# stm32-2inch40.net
KiCad netlist of a schematic drawn in EAGLE
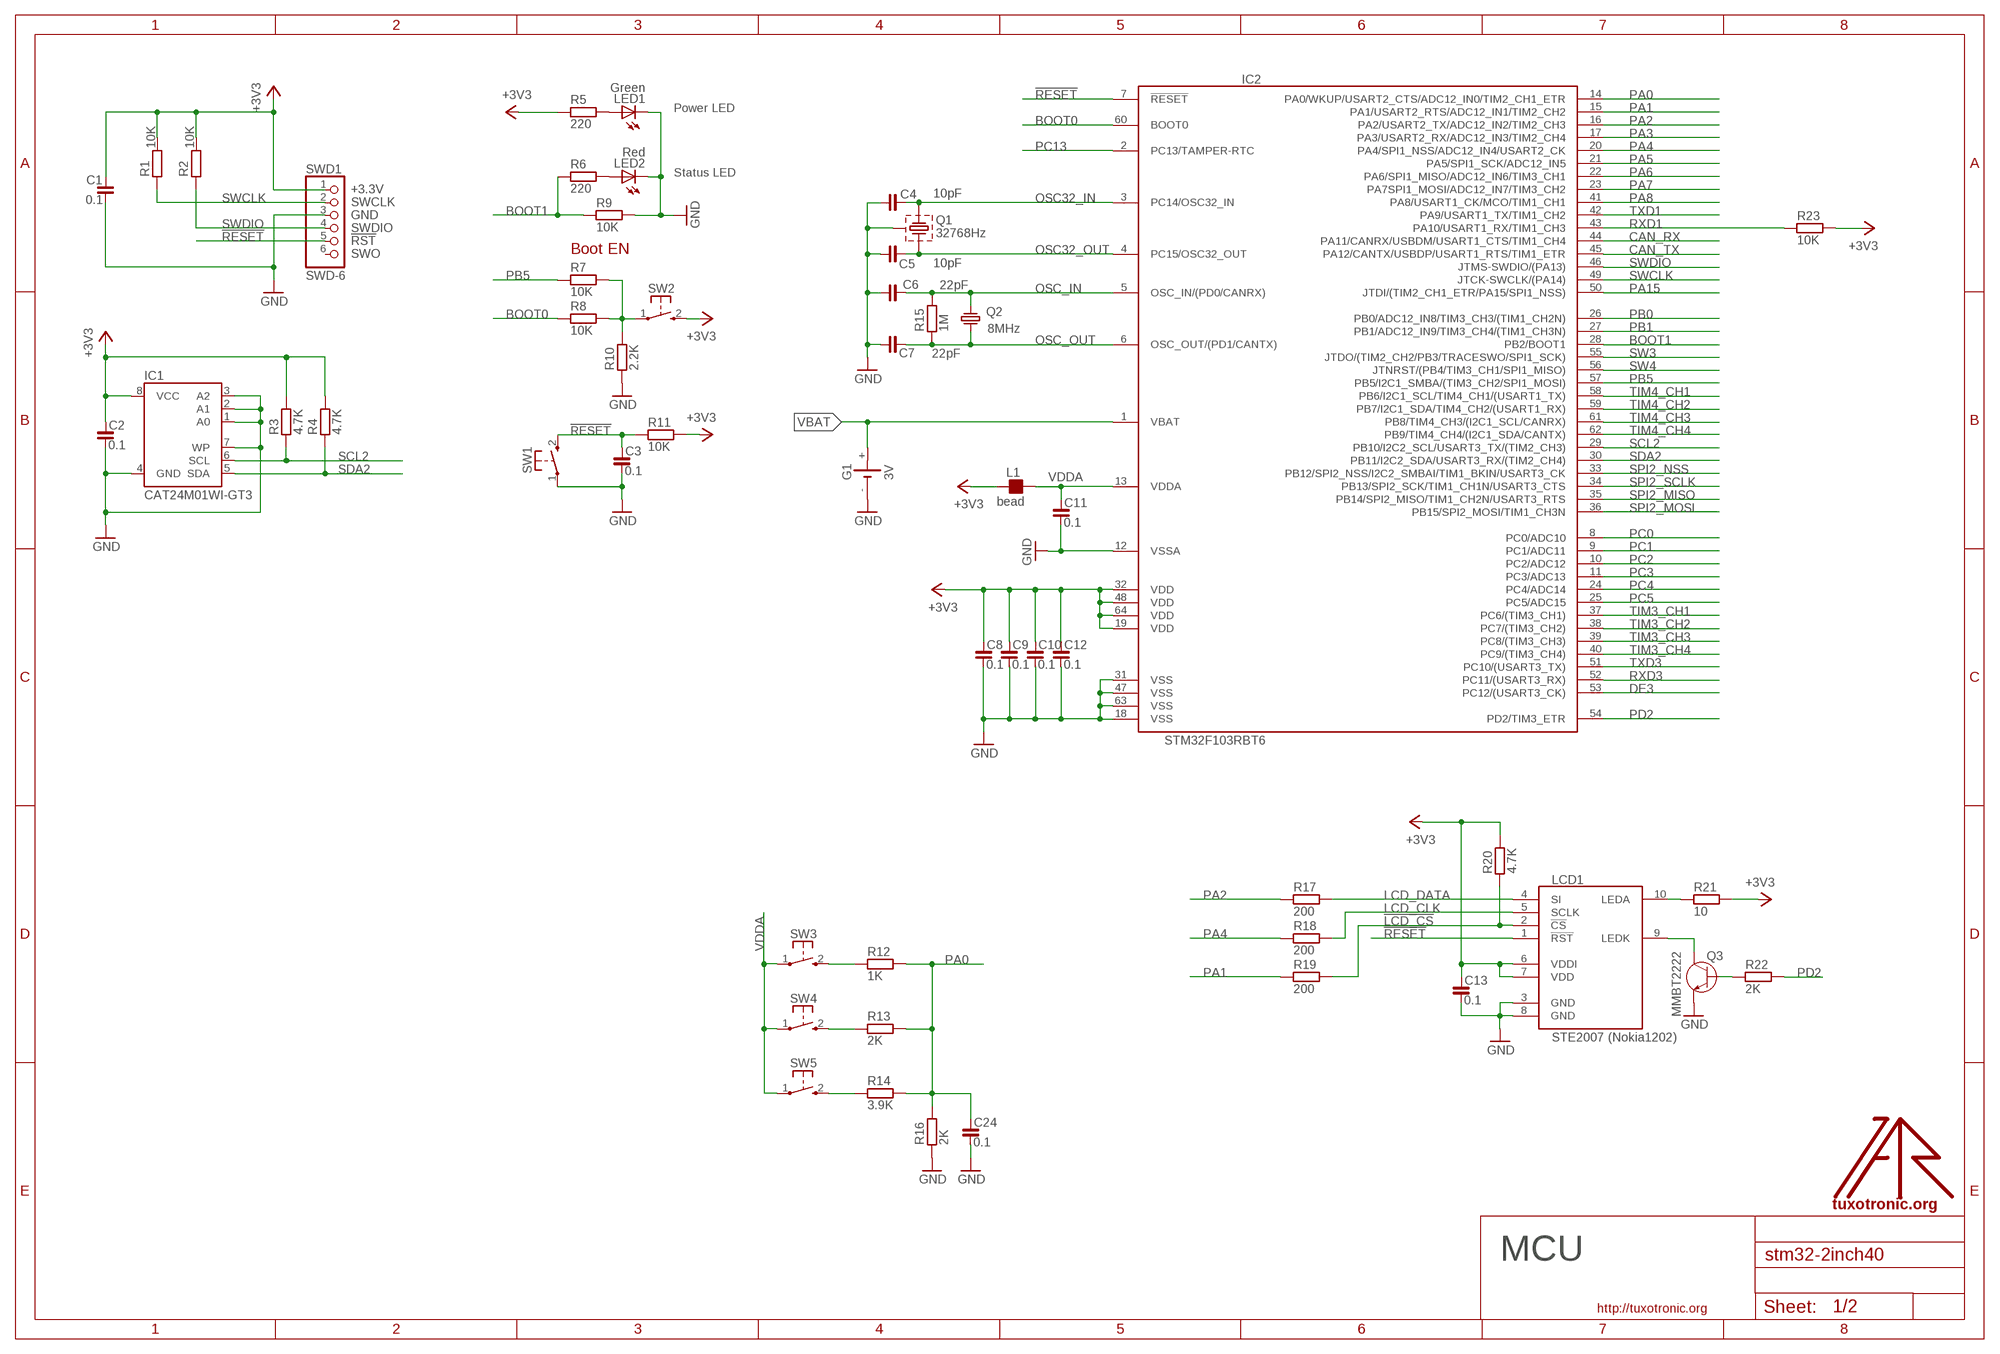
[diagram p0: schematic, sheet 1]
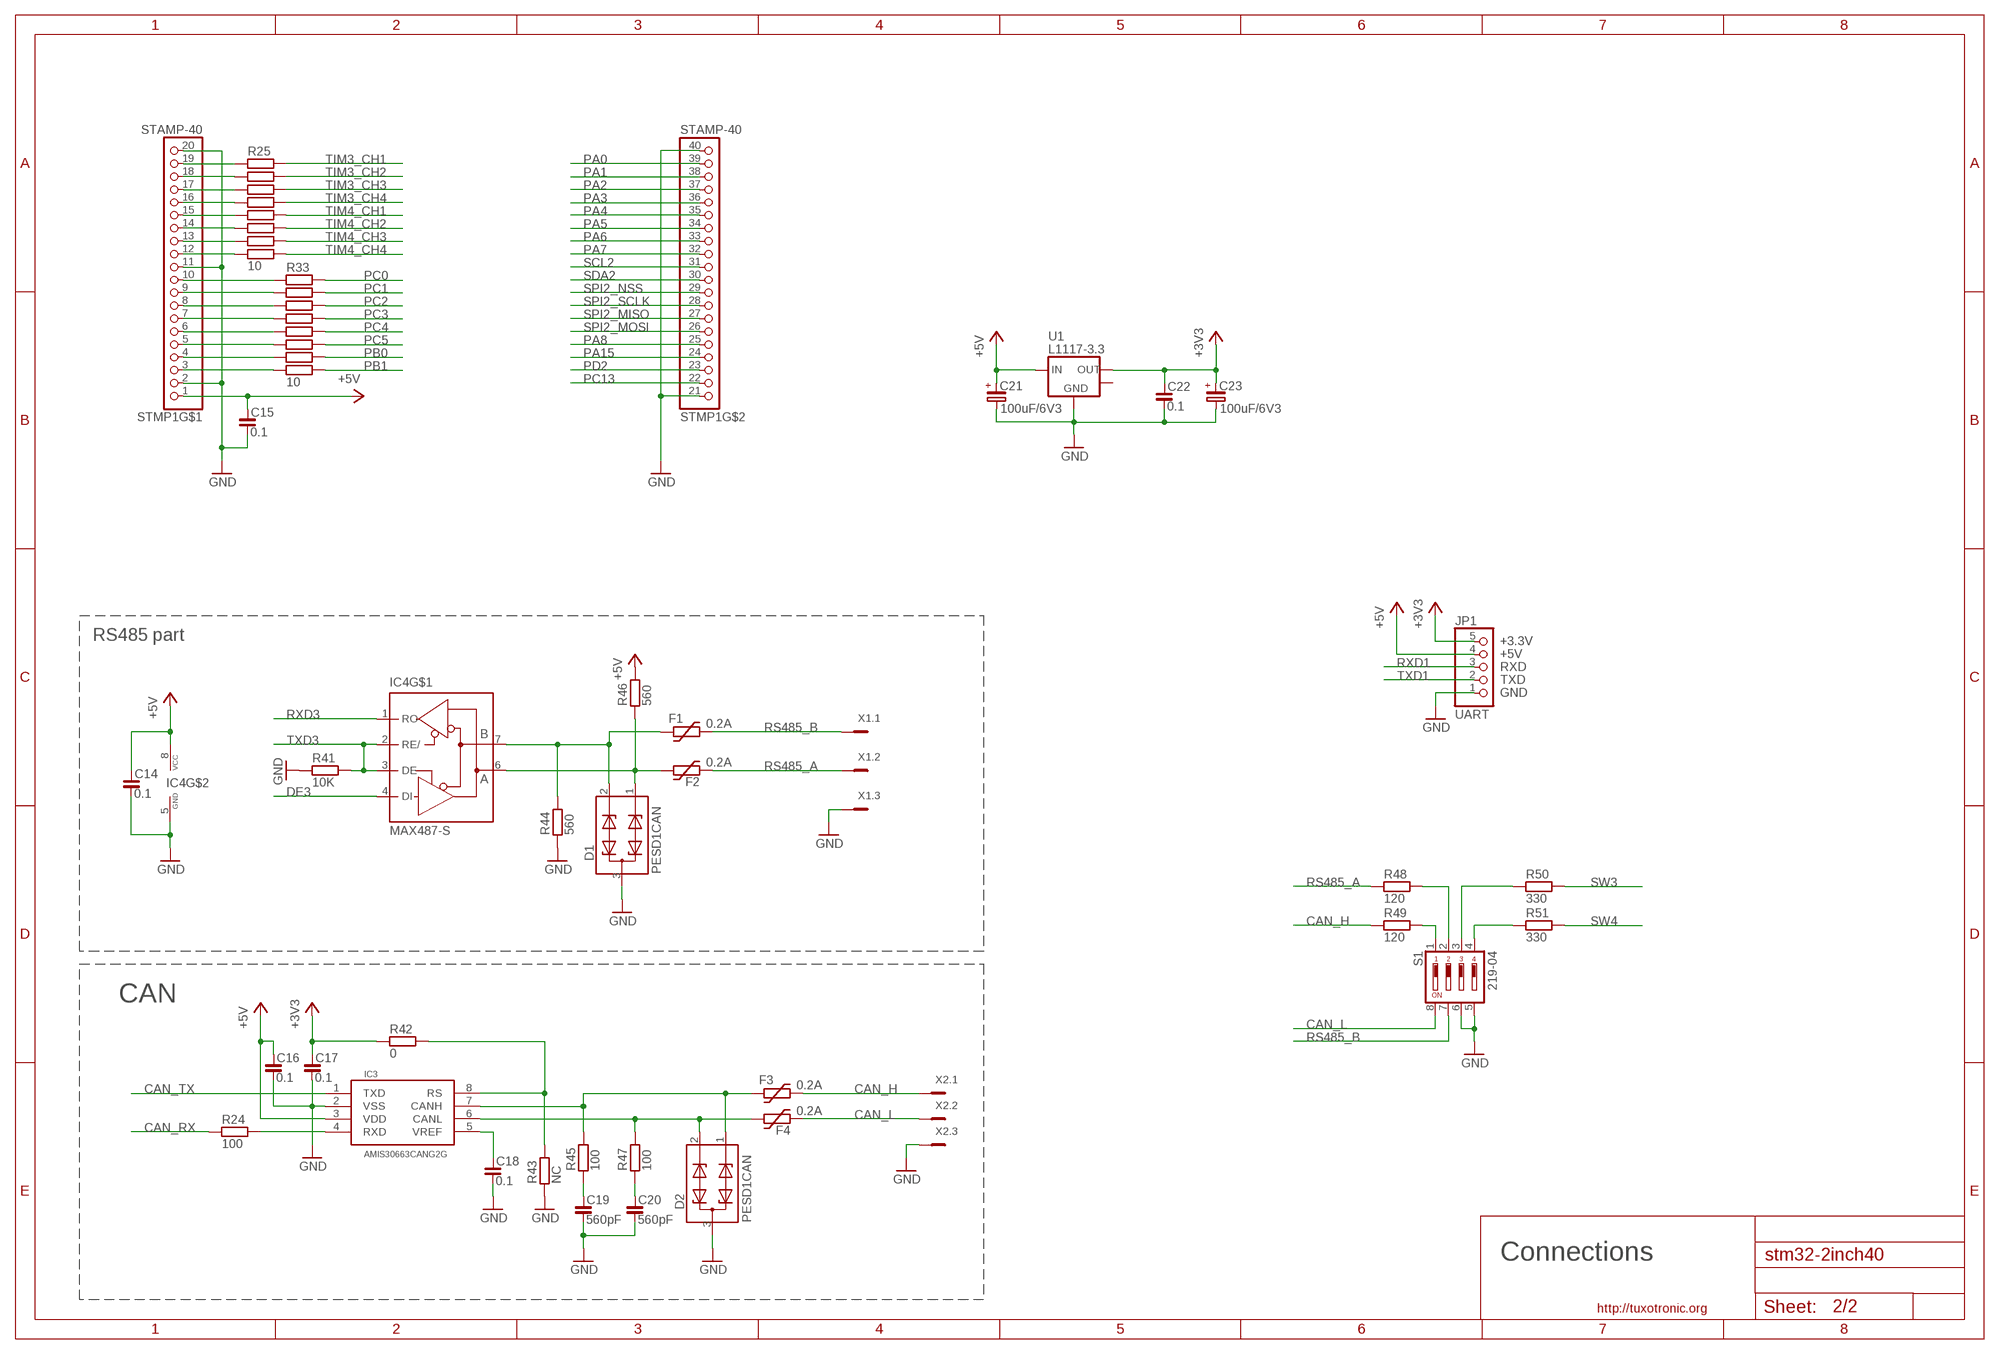
[diagram p1: schematic, sheet 2]

(export (version "E")
  (design (tool "Eeschema 10.0.6"))
  (components
    (comp (ref "C14")
      (value "0.1")
      (footprint "eagle-import:C0603")
      (libsource (lib "eagle-import") (part "C_0603"))
    )
    (comp (ref "C15")
      (value "0.1")
      (footprint "eagle-import:C0805")
      (libsource (lib "eagle-import") (part "C_0805"))
    )
    (comp (ref "C16")
      (value "0.1")
      (footprint "eagle-import:C0603")
      (libsource (lib "eagle-import") (part "C_0603"))
    )
    (comp (ref "C17")
      (value "0.1")
      (footprint "eagle-import:C0603")
      (libsource (lib "eagle-import") (part "C_0603"))
    )
    (comp (ref "C18")
      (value "0.1")
      (footprint "eagle-import:C0603")
      (libsource (lib "eagle-import") (part "C_0603"))
    )
    (comp (ref "C19")
      (value "560pF")
      (footprint "eagle-import:C0603")
      (libsource (lib "eagle-import") (part "C_0603"))
    )
    (comp (ref "C20")
      (value "560pF")
      (footprint "eagle-import:C0603")
      (libsource (lib "eagle-import") (part "C_0603"))
    )
    (comp (ref "C21")
      (value "100uF/6V3")
      (footprint "eagle-import:SMC_D")
      (libsource (lib "eagle-import") (part "CP_SMCD"))
    )
    (comp (ref "C22")
      (value "0.1")
      (footprint "eagle-import:C0805")
      (libsource (lib "eagle-import") (part "C_0805"))
    )
    (comp (ref "C23")
      (value "100uF/6V3")
      (footprint "eagle-import:SMC_D")
      (libsource (lib "eagle-import") (part "CP_SMCD"))
    )
    (comp (ref "D1")
      (value "PESD1CAN")
      (footprint "eagle-import:SOT23")
      (libsource (lib "eagle-import") (part "PESD1CAN"))
    )
    (comp (ref "D2")
      (value "PESD1CAN")
      (footprint "eagle-import:SOT23")
      (libsource (lib "eagle-import") (part "PESD1CAN"))
    )
    (comp (ref "F1")
      (value "0.2A")
      (footprint "eagle-import:1206L")
      (libsource (lib "eagle-import") (part "1206L"))
    )
    (comp (ref "F2")
      (value "0.2A")
      (footprint "eagle-import:1206L")
      (libsource (lib "eagle-import") (part "1206L"))
    )
    (comp (ref "F3")
      (value "0.2A")
      (footprint "eagle-import:1206L")
      (libsource (lib "eagle-import") (part "1206L"))
    )
    (comp (ref "F4")
      (value "0.2A")
      (footprint "eagle-import:1206L")
      (libsource (lib "eagle-import") (part "1206L"))
    )
    (comp (ref "IC3")
      (value "AMIS30663CANG2G")
      (footprint "eagle-import:SO08")
      (libsource (lib "eagle-import") (part "SN65HVD230"))
    )
    (comp (ref "IC4")
      (value "MAX487-S")
      (footprint "eagle-import:SO08")
      (libsource (lib "eagle-import") (part "MAX487-S"))
    )
    (comp (ref "JP1")
      (value "UART")
      (footprint "eagle-import:UART_1X05")
      (libsource (lib "eagle-import") (part "UART-5_2.54"))
    )
    (comp (ref "R24")
      (value "100")
      (footprint "eagle-import:R0603")
      (libsource (lib "eagle-import") (part "R_0603"))
    )
    (comp (ref "R25")
      (value "10")
      (footprint "eagle-import:R0603")
      (libsource (lib "eagle-import") (part "R_0603"))
    )
    (comp (ref "R26")
      (value "10")
      (footprint "eagle-import:R0603")
      (libsource (lib "eagle-import") (part "R_0603"))
    )
    (comp (ref "R27")
      (value "10")
      (footprint "eagle-import:R0603")
      (libsource (lib "eagle-import") (part "R_0603"))
    )
    (comp (ref "R28")
      (value "10")
      (footprint "eagle-import:R0603")
      (libsource (lib "eagle-import") (part "R_0603"))
    )
    (comp (ref "R29")
      (value "10")
      (footprint "eagle-import:R0603")
      (libsource (lib "eagle-import") (part "R_0603"))
    )
    (comp (ref "R30")
      (value "10")
      (footprint "eagle-import:R0603")
      (libsource (lib "eagle-import") (part "R_0603"))
    )
    (comp (ref "R31")
      (value "10")
      (footprint "eagle-import:R0603")
      (libsource (lib "eagle-import") (part "R_0603"))
    )
    (comp (ref "R32")
      (value "10")
      (footprint "eagle-import:R0603")
      (libsource (lib "eagle-import") (part "R_0603"))
    )
    (comp (ref "R33")
      (value "10")
      (footprint "eagle-import:R0603")
      (libsource (lib "eagle-import") (part "R_0603"))
    )
    (comp (ref "R34")
      (value "10")
      (footprint "eagle-import:R0603")
      (libsource (lib "eagle-import") (part "R_0603"))
    )
    (comp (ref "R35")
      (value "10")
      (footprint "eagle-import:R0603")
      (libsource (lib "eagle-import") (part "R_0603"))
    )
    (comp (ref "R36")
      (value "10")
      (footprint "eagle-import:R0603")
      (libsource (lib "eagle-import") (part "R_0603"))
    )
    (comp (ref "R37")
      (value "10")
      (footprint "eagle-import:R0603")
      (libsource (lib "eagle-import") (part "R_0603"))
    )
    (comp (ref "R38")
      (value "10")
      (footprint "eagle-import:R0603")
      (libsource (lib "eagle-import") (part "R_0603"))
    )
    (comp (ref "R39")
      (value "10")
      (footprint "eagle-import:R0603")
      (libsource (lib "eagle-import") (part "R_0603"))
    )
    (comp (ref "R40")
      (value "10")
      (footprint "eagle-import:R0603")
      (libsource (lib "eagle-import") (part "R_0603"))
    )
    (comp (ref "R41")
      (value "10K")
      (footprint "eagle-import:R0603")
      (libsource (lib "eagle-import") (part "R_0603"))
    )
    (comp (ref "R42")
      (value "0")
      (footprint "eagle-import:R0603")
      (libsource (lib "eagle-import") (part "R_0603"))
    )
    (comp (ref "R43")
      (value "NC")
      (footprint "eagle-import:R0603")
      (libsource (lib "eagle-import") (part "R_0603"))
    )
    (comp (ref "R44")
      (value "560")
      (footprint "eagle-import:R0603")
      (libsource (lib "eagle-import") (part "R_0603"))
    )
    (comp (ref "R45")
      (value "100")
      (footprint "eagle-import:R0603")
      (libsource (lib "eagle-import") (part "R_0603"))
    )
    (comp (ref "R46")
      (value "560")
      (footprint "eagle-import:R0603")
      (libsource (lib "eagle-import") (part "R_0603"))
    )
    (comp (ref "R47")
      (value "100")
      (footprint "eagle-import:R0603")
      (libsource (lib "eagle-import") (part "R_0603"))
    )
    (comp (ref "R48")
      (value "120")
      (footprint "eagle-import:R0805")
      (libsource (lib "eagle-import") (part "R_0805"))
    )
    (comp (ref "R49")
      (value "120")
      (footprint "eagle-import:R0805")
      (libsource (lib "eagle-import") (part "R_0805"))
    )
    (comp (ref "R50")
      (value "330")
      (footprint "eagle-import:R0603")
      (libsource (lib "eagle-import") (part "R_0603"))
    )
    (comp (ref "R51")
      (value "330")
      (footprint "eagle-import:R0603")
      (libsource (lib "eagle-import") (part "R_0603"))
    )
    (comp (ref "S1")
      (value "219-04")
      (footprint "eagle-import:CTS-219-04")
      (libsource (lib "eagle-import") (part "219-04"))
    )
    (comp (ref "STMP1")
      (value "STAMP-40")
      (footprint "eagle-import:STAMP-40")
      (libsource (lib "eagle-import") (part "STAMP-40"))
    )
    (comp (ref "U1")
      (value "L1117-3.3")
      (footprint "eagle-import:SOT223")
      (libsource (lib "eagle-import") (part "LM1117-3.3"))
    )
    (comp (ref "X1")
      (value "MCV3")
      (footprint "eagle-import:MCV3")
      (libsource (lib "eagle-import") (part "MCV3"))
    )
    (comp (ref "X2")
      (value "MCV3")
      (footprint "eagle-import:MCV3")
      (libsource (lib "eagle-import") (part "MCV3"))
    )
    (comp (ref "C1")
      (value "0.1")
      (footprint "eagle-import:C0603")
      (libsource (lib "eagle-import") (part "C_0603"))
    )
    (comp (ref "C2")
      (value "0.1")
      (footprint "eagle-import:C0603")
      (libsource (lib "eagle-import") (part "C_0603"))
    )
    (comp (ref "C3")
      (value "0.1")
      (footprint "eagle-import:C0603")
      (libsource (lib "eagle-import") (part "C_0603"))
    )
    (comp (ref "C4")
      (value "10pF")
      (footprint "eagle-import:C0603")
      (libsource (lib "eagle-import") (part "C_0603"))
    )
    (comp (ref "C5")
      (value "10pF")
      (footprint "eagle-import:C0603")
      (libsource (lib "eagle-import") (part "C_0603"))
    )
    (comp (ref "C6")
      (value "22pF")
      (footprint "eagle-import:C0603")
      (libsource (lib "eagle-import") (part "C_0603"))
    )
    (comp (ref "C7")
      (value "22pF")
      (footprint "eagle-import:C0603")
      (libsource (lib "eagle-import") (part "C_0603"))
    )
    (comp (ref "C8")
      (value "0.1")
      (footprint "eagle-import:C0603")
      (libsource (lib "eagle-import") (part "C_0603"))
    )
    (comp (ref "C9")
      (value "0.1")
      (footprint "eagle-import:C0603")
      (libsource (lib "eagle-import") (part "C_0603"))
    )
    (comp (ref "C10")
      (value "0.1")
      (footprint "eagle-import:C0603")
      (libsource (lib "eagle-import") (part "C_0603"))
    )
    (comp (ref "C11")
      (value "0.1")
      (footprint "eagle-import:C0603")
      (libsource (lib "eagle-import") (part "C_0603"))
    )
    (comp (ref "C12")
      (value "0.1")
      (footprint "eagle-import:C0603")
      (libsource (lib "eagle-import") (part "C_0603"))
    )
    (comp (ref "C13")
      (value "0.1")
      (footprint "eagle-import:C0603")
      (libsource (lib "eagle-import") (part "C_0603"))
    )
    (comp (ref "C24")
      (value "0.1")
      (footprint "eagle-import:C0603")
      (libsource (lib "eagle-import") (part "C_0603"))
    )
    (comp (ref "G1")
      (value "3V")
      (footprint "eagle-import:SMT1220")
      (libsource (lib "eagle-import") (part "1220SMT"))
    )
    (comp (ref "IC1")
      (value "CAT24M01WI-GT3")
      (footprint "eagle-import:SO08")
      (libsource (lib "eagle-import") (part "AT24CS256"))
    )
    (comp (ref "IC2")
      (value "STM32F103RBT6")
      (footprint "eagle-import:TQFP64")
      (libsource (lib "eagle-import") (part "STM32F103R"))
    )
    (comp (ref "L1")
      (value "bead")
      (footprint "eagle-import:L0603")
      (libsource (lib "eagle-import") (part "FB_0603"))
    )
    (comp (ref "LCD1")
      (value "STE2007 (Nokia1202)")
      (footprint "eagle-import:NOKIA1202LCD-EXT")
      (libsource (lib "eagle-import") (part "LCD1202-EXT"))
    )
    (comp (ref "LED1")
      (value "Green")
      (footprint "eagle-import:CHIP-LED0805")
      (libsource (lib "eagle-import") (part "LEDCHIP-LED0805"))
    )
    (comp (ref "LED2")
      (value "Red")
      (footprint "eagle-import:CHIP-LED0805")
      (libsource (lib "eagle-import") (part "LEDCHIP-LED0805"))
    )
    (comp (ref "Q1")
      (value "32768Hz")
      (footprint "eagle-import:TC38H-G")
      (libsource (lib "eagle-import") (part "CRSTL3-"))
    )
    (comp (ref "Q2")
      (value "8MHz")
      (footprint "eagle-import:HC49_S")
      (libsource (lib "eagle-import") (part "CRYSTAL-HC49S"))
    )
    (comp (ref "Q3")
      (value "MMBT2222")
      (footprint "eagle-import:SOT23")
      (libsource (lib "eagle-import") (part "MMBT2222"))
    )
    (comp (ref "R1")
      (value "10K")
      (footprint "eagle-import:R0603")
      (libsource (lib "eagle-import") (part "R_0603"))
    )
    (comp (ref "R2")
      (value "10K")
      (footprint "eagle-import:R0603")
      (libsource (lib "eagle-import") (part "R_0603"))
    )
    (comp (ref "R3")
      (value "4.7K")
      (footprint "eagle-import:R0603")
      (libsource (lib "eagle-import") (part "R_0603"))
    )
    (comp (ref "R4")
      (value "4.7K")
      (footprint "eagle-import:R0603")
      (libsource (lib "eagle-import") (part "R_0603"))
    )
    (comp (ref "R5")
      (value "220")
      (footprint "eagle-import:R0603")
      (libsource (lib "eagle-import") (part "R_0603"))
    )
    (comp (ref "R6")
      (value "220")
      (footprint "eagle-import:R0603")
      (libsource (lib "eagle-import") (part "R_0603"))
    )
    (comp (ref "R7")
      (value "10K")
      (footprint "eagle-import:R0603")
      (libsource (lib "eagle-import") (part "R_0603"))
    )
    (comp (ref "R8")
      (value "10K")
      (footprint "eagle-import:R0603")
      (libsource (lib "eagle-import") (part "R_0603"))
    )
    (comp (ref "R9")
      (value "10K")
      (footprint "eagle-import:R0603")
      (libsource (lib "eagle-import") (part "R_0603"))
    )
    (comp (ref "R10")
      (value "2.2K")
      (footprint "eagle-import:R0603")
      (libsource (lib "eagle-import") (part "R_0603"))
    )
    (comp (ref "R11")
      (value "10K")
      (footprint "eagle-import:R0603")
      (libsource (lib "eagle-import") (part "R_0603"))
    )
    (comp (ref "R12")
      (value "1K")
      (footprint "eagle-import:R0603")
      (libsource (lib "eagle-import") (part "R_0603"))
    )
    (comp (ref "R13")
      (value "2K")
      (footprint "eagle-import:R0603")
      (libsource (lib "eagle-import") (part "R_0603"))
    )
    (comp (ref "R14")
      (value "3.9K")
      (footprint "eagle-import:R0603")
      (libsource (lib "eagle-import") (part "R_0603"))
    )
    (comp (ref "R15")
      (value "1M")
      (footprint "eagle-import:R0603")
      (libsource (lib "eagle-import") (part "R_0603"))
    )
    (comp (ref "R16")
      (value "2K")
      (footprint "eagle-import:R0603")
      (libsource (lib "eagle-import") (part "R_0603"))
    )
    (comp (ref "R17")
      (value "200")
      (footprint "eagle-import:R0603")
      (libsource (lib "eagle-import") (part "R_0603"))
    )
    (comp (ref "R18")
      (value "200")
      (footprint "eagle-import:R0603")
      (libsource (lib "eagle-import") (part "R_0603"))
    )
    (comp (ref "R19")
      (value "200")
      (footprint "eagle-import:R0603")
      (libsource (lib "eagle-import") (part "R_0603"))
    )
    (comp (ref "R20")
      (value "4.7K")
      (footprint "eagle-import:R0603")
      (libsource (lib "eagle-import") (part "R_0603"))
    )
    (comp (ref "R21")
      (value "10")
      (footprint "eagle-import:R0603")
      (libsource (lib "eagle-import") (part "R_0603"))
    )
    (comp (ref "R22")
      (value "2K")
      (footprint "eagle-import:R0603")
      (libsource (lib "eagle-import") (part "R_0603"))
    )
    (comp (ref "R23")
      (value "10K")
      (footprint "eagle-import:R0603")
      (libsource (lib "eagle-import") (part "R_0603"))
    )
    (comp (ref "SW1")
      (value "KSS-2EG4430")
      (footprint "eagle-import:KSS-2EG4430")
      (libsource (lib "eagle-import") (part "KSS-2EG4430"))
    )
    (comp (ref "SW2")
      (value "KSS-2EG4430")
      (footprint "eagle-import:KSS-2EG4430")
      (libsource (lib "eagle-import") (part "KSS-2EG4430"))
    )
    (comp (ref "SW3")
      (value "KSS-2EG4430")
      (footprint "eagle-import:KSS-2EG4430")
      (libsource (lib "eagle-import") (part "KSS-2EG4430"))
    )
    (comp (ref "SW4")
      (value "KSS-2EG4430")
      (footprint "eagle-import:KSS-2EG4430")
      (libsource (lib "eagle-import") (part "KSS-2EG4430"))
    )
    (comp (ref "SW5")
      (value "KSS-2EG4430")
      (footprint "eagle-import:KSS-2EG4430")
      (libsource (lib "eagle-import") (part "KSS-2EG4430"))
    )
    (comp (ref "SWD1")
      (value "SWD-6")
      (footprint "eagle-import:JTAG6PIN")
      (libsource (lib "eagle-import") (part "SWD-6"))
    )
    (comp (ref "U$1")
      (value "LOGO")
      (footprint "eagle-import:TT_LOGO")
      (libsource (lib "eagle-import") (part "LOGO"))
    )
  )
  (nets
    (net (code "1") (name "+3V3") (class "Default")
      (node (ref "C1") (pin "1") (pinfunction "1_1") (pintype "passive"))
      (node (ref "C10") (pin "1") (pinfunction "1_1") (pintype "passive"))
      (node (ref "C12") (pin "1") (pinfunction "1_1") (pintype "passive"))
      (node (ref "C13") (pin "1") (pinfunction "1_1") (pintype "passive"))
      (node (ref "C17") (pin "1") (pinfunction "1_1") (pintype "passive"))
      (node (ref "C2") (pin "1") (pinfunction "1_1") (pintype "passive"))
      (node (ref "C22") (pin "1") (pinfunction "1_1") (pintype "passive"))
      (node (ref "C23") (pin "+") (pinfunction "+_+") (pintype "passive"))
      (node (ref "C8") (pin "1") (pinfunction "1_1") (pintype "passive"))
      (node (ref "C9") (pin "1") (pinfunction "1_1") (pintype "passive"))
      (node (ref "IC1") (pin "8") (pinfunction "VCC_8") (pintype "power_in"))
      (node (ref "IC2") (pin "19") (pinfunction "VDD_19") (pintype "power_in"))
      (node (ref "IC2") (pin "32") (pinfunction "VDD_32") (pintype "power_in"))
      (node (ref "IC2") (pin "48") (pinfunction "VDD_48") (pintype "power_in"))
      (node (ref "IC2") (pin "64") (pinfunction "VDD_64") (pintype "power_in"))
      (node (ref "JP1") (pin "5") (pinfunction "5_5") (pintype "passive"))
      (node (ref "L1") (pin "1") (pinfunction "1_1") (pintype "passive"))
      (node (ref "LCD1") (pin "6") (pinfunction "VDDI_6") (pintype "power_in"))
      (node (ref "LCD1") (pin "7") (pinfunction "VDD_7") (pintype "power_in"))
      (node (ref "R1") (pin "2") (pinfunction "2_2") (pintype "passive"))
      (node (ref "R11") (pin "2") (pinfunction "2_2") (pintype "passive"))
      (node (ref "R2") (pin "2") (pinfunction "2_2") (pintype "passive"))
      (node (ref "R20") (pin "2") (pinfunction "2_2") (pintype "passive"))
      (node (ref "R21") (pin "2") (pinfunction "2_2") (pintype "passive"))
      (node (ref "R23") (pin "2") (pinfunction "2_2") (pintype "passive"))
      (node (ref "R3") (pin "2") (pinfunction "2_2") (pintype "passive"))
      (node (ref "R4") (pin "2") (pinfunction "2_2") (pintype "passive"))
      (node (ref "R42") (pin "1") (pinfunction "1_1") (pintype "passive"))
      (node (ref "R5") (pin "1") (pinfunction "1_1") (pintype "passive"))
      (node (ref "SW2") (pin "2") (pinfunction "S_2") (pintype "passive"))
      (node (ref "SWD1") (pin "1") (pinfunction "1_1") (pintype "passive"))
      (node (ref "U1") (pin "2") (pinfunction "OUT_2") (pintype "power_in"))
    )
    (net (code "2") (name "+5V") (class "Default")
      (node (ref "C14") (pin "1") (pinfunction "1_1") (pintype "passive"))
      (node (ref "C15") (pin "1") (pinfunction "1_1") (pintype "passive"))
      (node (ref "C16") (pin "1") (pinfunction "1_1") (pintype "passive"))
      (node (ref "C21") (pin "+") (pinfunction "+_+") (pintype "passive"))
      (node (ref "IC3") (pin "3") (pinfunction "VDD_3") (pintype "power_in"))
      (node (ref "IC4") (pin "8") (pinfunction "VCC_8") (pintype "power_in"))
      (node (ref "JP1") (pin "4") (pinfunction "4_4") (pintype "passive"))
      (node (ref "R46") (pin "2") (pinfunction "2_2") (pintype "passive"))
      (node (ref "STMP1") (pin "1") (pinfunction "1_1") (pintype "passive"))
      (node (ref "U1") (pin "3") (pinfunction "IN_3") (pintype "power_in"))
    )
    (net (code "3") (name "BOOT0") (class "Default")
      (node (ref "IC2") (pin "60") (pinfunction "BOOT0_60") (pintype "input"))
      (node (ref "R8") (pin "1") (pinfunction "1_1") (pintype "passive"))
    )
    (net (code "4") (name "BOOT1") (class "Default")
      (node (ref "IC2") (pin "28") (pinfunction "PB2/BOOT1_28") (pintype "bidirectional"))
      (node (ref "R6") (pin "1") (pinfunction "1_1") (pintype "passive"))
      (node (ref "R9") (pin "1") (pinfunction "1_1") (pintype "passive"))
    )
    (net (code "5") (name "CAN_H") (class "Default")
      (node (ref "F3") (pin "P$2") (pinfunction "2_P$2") (pintype "passive"))
      (node (ref "R49") (pin "1") (pinfunction "1_1") (pintype "passive"))
      (node (ref "X2") (pin "1") (pinfunction "SK_1") (pintype "passive"))
    )
    (net (code "6") (name "CAN_L") (class "Default")
      (node (ref "F4") (pin "P$2") (pinfunction "2_P$2") (pintype "passive"))
      (node (ref "S1") (pin "8") (pinfunction "8_8") (pintype "passive"))
      (node (ref "X2") (pin "2") (pinfunction "SK_2") (pintype "passive"))
    )
    (net (code "7") (name "CAN_RX") (class "Default")
      (node (ref "IC2") (pin "44") (pinfunction "PA11/CANRX/USBDM/USART1_CTS/TIM1_CH4_44") (pintype "bidirectional"))
      (node (ref "R24") (pin "1") (pinfunction "1_1") (pintype "passive"))
    )
    (net (code "8") (name "CAN_TX") (class "Default")
      (node (ref "IC2") (pin "45") (pinfunction "PA12/CANTX/USBDP/USART1_RTS/TIM1_ETR_45") (pintype "bidirectional"))
      (node (ref "IC3") (pin "1") (pinfunction "TXD_1") (pintype "input"))
    )
    (net (code "9") (name "DE3") (class "Default")
      (node (ref "IC2") (pin "53") (pinfunction "PC12/(USART3_CK)_53") (pintype "bidirectional"))
      (node (ref "IC4") (pin "4") (pinfunction "DI_4") (pintype "input"))
    )
    (net (code "10") (name "GND") (class "Default")
      (node (ref "C1") (pin "2") (pinfunction "2_2") (pintype "passive"))
      (node (ref "C10") (pin "2") (pinfunction "2_2") (pintype "passive"))
      (node (ref "C11") (pin "2") (pinfunction "2_2") (pintype "passive"))
      (node (ref "C12") (pin "2") (pinfunction "2_2") (pintype "passive"))
      (node (ref "C13") (pin "2") (pinfunction "2_2") (pintype "passive"))
      (node (ref "C14") (pin "2") (pinfunction "2_2") (pintype "passive"))
      (node (ref "C15") (pin "2") (pinfunction "2_2") (pintype "passive"))
      (node (ref "C16") (pin "2") (pinfunction "2_2") (pintype "passive"))
      (node (ref "C17") (pin "2") (pinfunction "2_2") (pintype "passive"))
      (node (ref "C18") (pin "2") (pinfunction "2_2") (pintype "passive"))
      (node (ref "C19") (pin "2") (pinfunction "2_2") (pintype "passive"))
      (node (ref "C2") (pin "2") (pinfunction "2_2") (pintype "passive"))
      (node (ref "C20") (pin "2") (pinfunction "2_2") (pintype "passive"))
      (node (ref "C21") (pin "-") (pinfunction "-_-") (pintype "passive"))
      (node (ref "C22") (pin "2") (pinfunction "2_2") (pintype "passive"))
      (node (ref "C23") (pin "-") (pinfunction "-_-") (pintype "passive"))
      (node (ref "C24") (pin "2") (pinfunction "2_2") (pintype "passive"))
      (node (ref "C3") (pin "2") (pinfunction "2_2") (pintype "passive"))
      (node (ref "C4") (pin "2") (pinfunction "2_2") (pintype "passive"))
      (node (ref "C5") (pin "2") (pinfunction "2_2") (pintype "passive"))
      (node (ref "C6") (pin "2") (pinfunction "2_2") (pintype "passive"))
      (node (ref "C7") (pin "2") (pinfunction "2_2") (pintype "passive"))
      (node (ref "C8") (pin "2") (pinfunction "2_2") (pintype "passive"))
      (node (ref "C9") (pin "2") (pinfunction "2_2") (pintype "passive"))
      (node (ref "D1") (pin "3") (pinfunction "3_3") (pintype "passive"))
      (node (ref "D2") (pin "3") (pinfunction "3_3") (pintype "passive"))
      (node (ref "G1") (pin "-") (pinfunction "-_-") (pintype "passive"))
      (node (ref "IC1") (pin "1") (pinfunction "A0_1") (pintype "input"))
      (node (ref "IC1") (pin "2") (pinfunction "A1_2") (pintype "input"))
      (node (ref "IC1") (pin "3") (pinfunction "A2_3") (pintype "input"))
      (node (ref "IC1") (pin "4") (pinfunction "GND_4") (pintype "power_in"))
      (node (ref "IC1") (pin "7") (pinfunction "WP_7") (pintype "input"))
      (node (ref "IC2") (pin "12") (pinfunction "VSSA_12") (pintype "power_in"))
      (node (ref "IC2") (pin "18") (pinfunction "VSS_18") (pintype "power_in"))
      (node (ref "IC2") (pin "31") (pinfunction "VSS_31") (pintype "power_in"))
      (node (ref "IC2") (pin "47") (pinfunction "VSS_47") (pintype "power_in"))
      (node (ref "IC2") (pin "63") (pinfunction "VSS_63") (pintype "power_in"))
      (node (ref "IC3") (pin "2") (pinfunction "VSS_2") (pintype "power_in"))
      (node (ref "IC4") (pin "5") (pinfunction "GND_5") (pintype "power_in"))
      (node (ref "JP1") (pin "1") (pinfunction "1_1") (pintype "passive"))
      (node (ref "LCD1") (pin "3") (pinfunction "GND_3") (pintype "power_in"))
      (node (ref "LCD1") (pin "8") (pinfunction "GND_8") (pintype "power_in"))
      (node (ref "LED1") (pin "C") (pinfunction "C_C") (pintype "passive"))
      (node (ref "LED2") (pin "C") (pinfunction "C_C") (pintype "passive"))
      (node (ref "Q1") (pin "GND") (pinfunction "P$1_GND") (pintype "passive"))
      (node (ref "Q3") (pin "2") (pinfunction "E_2") (pintype "passive"))
      (node (ref "R10") (pin "1") (pinfunction "1_1") (pintype "passive"))
      (node (ref "R16") (pin "1") (pinfunction "1_1") (pintype "passive"))
      (node (ref "R41") (pin "1") (pinfunction "1_1") (pintype "passive"))
      (node (ref "R43") (pin "1") (pinfunction "1_1") (pintype "passive"))
      (node (ref "R44") (pin "1") (pinfunction "1_1") (pintype "passive"))
      (node (ref "R9") (pin "2") (pinfunction "2_2") (pintype "passive"))
      (node (ref "S1") (pin "5") (pinfunction "5_5") (pintype "passive"))
      (node (ref "S1") (pin "6") (pinfunction "6_6") (pintype "passive"))
      (node (ref "STMP1") (pin "11") (pinfunction "11_11") (pintype "passive"))
      (node (ref "STMP1") (pin "2") (pinfunction "2_2") (pintype "passive"))
      (node (ref "STMP1") (pin "20") (pinfunction "20_20") (pintype "passive"))
      (node (ref "STMP1") (pin "21") (pinfunction "1_21") (pintype "passive"))
      (node (ref "STMP1") (pin "40") (pinfunction "20_40") (pintype "passive"))
      (node (ref "SW1") (pin "1") (pinfunction "P_1") (pintype "passive"))
      (node (ref "SWD1") (pin "3") (pinfunction "3_3") (pintype "passive"))
      (node (ref "U1") (pin "1") (pinfunction "GND_1") (pintype "power_in"))
      (node (ref "X1") (pin "3") (pinfunction "SK_3") (pintype "passive"))
      (node (ref "X2") (pin "3") (pinfunction "SK_3") (pintype "passive"))
    )
    (net (code "11") (name "LCD_CLK") (class "Default")
      (node (ref "LCD1") (pin "5") (pinfunction "SCLK_5") (pintype "input"))
      (node (ref "R18") (pin "2") (pinfunction "2_2") (pintype "passive"))
    )
    (net (code "12") (name "LCD_DATA") (class "Default")
      (node (ref "LCD1") (pin "4") (pinfunction "SI_4") (pintype "input"))
      (node (ref "R17") (pin "2") (pinfunction "2_2") (pintype "passive"))
    )
    (net (code "13") (name "Net-(C19-Pad1)") (class "Default")
      (node (ref "C19") (pin "1") (pinfunction "1_1") (pintype "passive"))
      (node (ref "R45") (pin "1") (pinfunction "1_1") (pintype "passive"))
    )
    (net (code "14") (name "Net-(C20-Pad1)") (class "Default")
      (node (ref "C20") (pin "1") (pinfunction "1_1") (pintype "passive"))
      (node (ref "R47") (pin "1") (pinfunction "1_1") (pintype "passive"))
    )
    (net (code "15") (name "Net-(F1-1)") (class "Default")
      (node (ref "D1") (pin "2") (pinfunction "2_2") (pintype "passive"))
      (node (ref "F1") (pin "P$1") (pinfunction "1_P$1") (pintype "passive"))
      (node (ref "IC4") (pin "7") (pinfunction "B_7") (pintype "passive"))
      (node (ref "R44") (pin "2") (pinfunction "2_2") (pintype "passive"))
    )
    (net (code "16") (name "Net-(F2-1)") (class "Default")
      (node (ref "D1") (pin "1") (pinfunction "1_1") (pintype "passive"))
      (node (ref "F2") (pin "P$1") (pinfunction "1_P$1") (pintype "passive"))
      (node (ref "IC4") (pin "6") (pinfunction "A_6") (pintype "passive"))
      (node (ref "R46") (pin "1") (pinfunction "1_1") (pintype "passive"))
    )
    (net (code "17") (name "Net-(F3-1)") (class "Default")
      (node (ref "D2") (pin "1") (pinfunction "1_1") (pintype "passive"))
      (node (ref "F3") (pin "P$1") (pinfunction "1_P$1") (pintype "passive"))
      (node (ref "IC3") (pin "7") (pinfunction "CANH_7") (pintype "bidirectional"))
      (node (ref "R45") (pin "2") (pinfunction "2_2") (pintype "passive"))
    )
    (net (code "18") (name "Net-(F4-1)") (class "Default")
      (node (ref "D2") (pin "2") (pinfunction "2_2") (pintype "passive"))
      (node (ref "F4") (pin "P$1") (pinfunction "1_P$1") (pintype "passive"))
      (node (ref "IC3") (pin "6") (pinfunction "CANL_6") (pintype "bidirectional"))
      (node (ref "R47") (pin "2") (pinfunction "2_2") (pintype "passive"))
    )
    (net (code "19") (name "Net-(IC3-RS)") (class "Default")
      (node (ref "IC3") (pin "8") (pinfunction "RS_8") (pintype "input"))
      (node (ref "R42") (pin "2") (pinfunction "2_2") (pintype "passive"))
      (node (ref "R43") (pin "2") (pinfunction "2_2") (pintype "passive"))
    )
    (net (code "20") (name "Net-(IC3-RXD)") (class "Default")
      (node (ref "IC3") (pin "4") (pinfunction "RXD_4") (pintype "output"))
      (node (ref "R24") (pin "2") (pinfunction "2_2") (pintype "passive"))
    )
    (net (code "21") (name "Net-(IC3-VREF)") (class "Default")
      (node (ref "C18") (pin "1") (pinfunction "1_1") (pintype "passive"))
      (node (ref "IC3") (pin "5") (pinfunction "VREF_5") (pintype "passive"))
    )
    (net (code "22") (name "Net-(LCD1-LEDA)") (class "Default")
      (node (ref "LCD1") (pin "10") (pinfunction "LEDA_10") (pintype "passive"))
      (node (ref "R21") (pin "1") (pinfunction "1_1") (pintype "passive"))
    )
    (net (code "23") (name "Net-(LCD1-LEDK)") (class "Default")
      (node (ref "LCD1") (pin "9") (pinfunction "LEDK_9") (pintype "passive"))
      (node (ref "Q3") (pin "3") (pinfunction "C_3") (pintype "passive"))
    )
    (net (code "24") (name "Net-(LED1-PadA)") (class "Default")
      (node (ref "LED1") (pin "A") (pinfunction "A_A") (pintype "passive"))
      (node (ref "R5") (pin "2") (pinfunction "2_2") (pintype "passive"))
    )
    (net (code "25") (name "Net-(LED2-PadA)") (class "Default")
      (node (ref "LED2") (pin "A") (pinfunction "A_A") (pintype "passive"))
      (node (ref "R6") (pin "2") (pinfunction "2_2") (pintype "passive"))
    )
    (net (code "26") (name "Net-(Q3-B)") (class "Default")
      (node (ref "Q3") (pin "1") (pinfunction "B_1") (pintype "passive"))
      (node (ref "R22") (pin "1") (pinfunction "1_1") (pintype "passive"))
    )
    (net (code "27") (name "Net-(R25-Pad1)") (class "Default")
      (node (ref "R25") (pin "1") (pinfunction "1_1") (pintype "passive"))
      (node (ref "STMP1") (pin "19") (pinfunction "19_19") (pintype "passive"))
    )
    (net (code "28") (name "Net-(R26-Pad1)") (class "Default")
      (node (ref "R26") (pin "1") (pinfunction "1_1") (pintype "passive"))
      (node (ref "STMP1") (pin "18") (pinfunction "18_18") (pintype "passive"))
    )
    (net (code "29") (name "Net-(R27-Pad1)") (class "Default")
      (node (ref "R27") (pin "1") (pinfunction "1_1") (pintype "passive"))
      (node (ref "STMP1") (pin "17") (pinfunction "17_17") (pintype "passive"))
    )
    (net (code "30") (name "Net-(R28-Pad1)") (class "Default")
      (node (ref "R28") (pin "1") (pinfunction "1_1") (pintype "passive"))
      (node (ref "STMP1") (pin "16") (pinfunction "16_16") (pintype "passive"))
    )
    (net (code "31") (name "Net-(R29-Pad1)") (class "Default")
      (node (ref "R29") (pin "1") (pinfunction "1_1") (pintype "passive"))
      (node (ref "STMP1") (pin "15") (pinfunction "15_15") (pintype "passive"))
    )
    (net (code "32") (name "Net-(R30-Pad1)") (class "Default")
      (node (ref "R30") (pin "1") (pinfunction "1_1") (pintype "passive"))
      (node (ref "STMP1") (pin "14") (pinfunction "14_14") (pintype "passive"))
    )
    (net (code "33") (name "Net-(R31-Pad1)") (class "Default")
      (node (ref "R31") (pin "1") (pinfunction "1_1") (pintype "passive"))
      (node (ref "STMP1") (pin "13") (pinfunction "13_13") (pintype "passive"))
    )
    (net (code "34") (name "Net-(R32-Pad1)") (class "Default")
      (node (ref "R32") (pin "1") (pinfunction "1_1") (pintype "passive"))
      (node (ref "STMP1") (pin "12") (pinfunction "12_12") (pintype "passive"))
    )
    (net (code "35") (name "Net-(R33-Pad1)") (class "Default")
      (node (ref "R33") (pin "1") (pinfunction "1_1") (pintype "passive"))
      (node (ref "STMP1") (pin "10") (pinfunction "10_10") (pintype "passive"))
    )
    (net (code "36") (name "Net-(R34-Pad1)") (class "Default")
      (node (ref "R34") (pin "1") (pinfunction "1_1") (pintype "passive"))
      (node (ref "STMP1") (pin "9") (pinfunction "9_9") (pintype "passive"))
    )
    (net (code "37") (name "Net-(R35-Pad1)") (class "Default")
      (node (ref "R35") (pin "1") (pinfunction "1_1") (pintype "passive"))
      (node (ref "STMP1") (pin "8") (pinfunction "8_8") (pintype "passive"))
    )
    (net (code "38") (name "Net-(R36-Pad1)") (class "Default")
      (node (ref "R36") (pin "1") (pinfunction "1_1") (pintype "passive"))
      (node (ref "STMP1") (pin "7") (pinfunction "7_7") (pintype "passive"))
    )
    (net (code "39") (name "Net-(R37-Pad1)") (class "Default")
      (node (ref "R37") (pin "1") (pinfunction "1_1") (pintype "passive"))
      (node (ref "STMP1") (pin "6") (pinfunction "6_6") (pintype "passive"))
    )
    (net (code "40") (name "Net-(R38-Pad1)") (class "Default")
      (node (ref "R38") (pin "1") (pinfunction "1_1") (pintype "passive"))
      (node (ref "STMP1") (pin "5") (pinfunction "5_5") (pintype "passive"))
    )
    (net (code "41") (name "Net-(R39-Pad1)") (class "Default")
      (node (ref "R39") (pin "1") (pinfunction "1_1") (pintype "passive"))
      (node (ref "STMP1") (pin "4") (pinfunction "4_4") (pintype "passive"))
    )
    (net (code "42") (name "Net-(R40-Pad1)") (class "Default")
      (node (ref "R40") (pin "1") (pinfunction "1_1") (pintype "passive"))
      (node (ref "STMP1") (pin "3") (pinfunction "3_3") (pintype "passive"))
    )
    (net (code "43") (name "Net-(R48-Pad2)") (class "Default")
      (node (ref "R48") (pin "2") (pinfunction "2_2") (pintype "passive"))
      (node (ref "S1") (pin "2") (pinfunction "2_2") (pintype "passive"))
    )
    (net (code "44") (name "Net-(R49-Pad2)") (class "Default")
      (node (ref "R49") (pin "2") (pinfunction "2_2") (pintype "passive"))
      (node (ref "S1") (pin "1") (pinfunction "1_1") (pintype "passive"))
    )
    (net (code "45") (name "Net-(R50-Pad1)") (class "Default")
      (node (ref "R50") (pin "1") (pinfunction "1_1") (pintype "passive"))
      (node (ref "S1") (pin "3") (pinfunction "3_3") (pintype "passive"))
    )
    (net (code "46") (name "Net-(R51-Pad1)") (class "Default")
      (node (ref "R51") (pin "1") (pinfunction "1_1") (pintype "passive"))
      (node (ref "S1") (pin "4") (pinfunction "4_4") (pintype "passive"))
    )
    (net (code "47") (name "Net-(SW2-P)") (class "Default")
      (node (ref "R10") (pin "2") (pinfunction "2_2") (pintype "passive"))
      (node (ref "R7") (pin "2") (pinfunction "2_2") (pintype "passive"))
      (node (ref "R8") (pin "2") (pinfunction "2_2") (pintype "passive"))
      (node (ref "SW2") (pin "1") (pinfunction "P_1") (pintype "passive"))
    )
    (net (code "48") (name "Net-(SW3-S)") (class "Default")
      (node (ref "R12") (pin "1") (pinfunction "1_1") (pintype "passive"))
      (node (ref "SW3") (pin "2") (pinfunction "S_2") (pintype "passive"))
    )
    (net (code "49") (name "Net-(SW4-S)") (class "Default")
      (node (ref "R13") (pin "1") (pinfunction "1_1") (pintype "passive"))
      (node (ref "SW4") (pin "2") (pinfunction "S_2") (pintype "passive"))
    )
    (net (code "50") (name "Net-(SW5-S)") (class "Default")
      (node (ref "R14") (pin "1") (pinfunction "1_1") (pintype "passive"))
      (node (ref "SW5") (pin "2") (pinfunction "S_2") (pintype "passive"))
    )
    (net (code "51") (name "OSC32_IN") (class "Default")
      (node (ref "C4") (pin "1") (pinfunction "1_1") (pintype "passive"))
      (node (ref "IC2") (pin "3") (pinfunction "PC14/OSC32_IN_3") (pintype "bidirectional"))
      (node (ref "Q1") (pin "2") (pinfunction "2_2") (pintype "passive"))
    )
    (net (code "52") (name "OSC32_OUT") (class "Default")
      (node (ref "C5") (pin "1") (pinfunction "1_1") (pintype "passive"))
      (node (ref "IC2") (pin "4") (pinfunction "PC15/OSC32_OUT_4") (pintype "bidirectional"))
      (node (ref "Q1") (pin "1") (pinfunction "1_1") (pintype "passive"))
    )
    (net (code "53") (name "OSC_IN") (class "Default")
      (node (ref "C6") (pin "1") (pinfunction "1_1") (pintype "passive"))
      (node (ref "IC2") (pin "5") (pinfunction "OSC_IN/(PD0/CANRX)_5") (pintype "input"))
      (node (ref "Q2") (pin "1") (pinfunction "1_1") (pintype "passive"))
      (node (ref "R15") (pin "2") (pinfunction "2_2") (pintype "passive"))
    )
    (net (code "54") (name "OSC_OUT") (class "Default")
      (node (ref "C7") (pin "1") (pinfunction "1_1") (pintype "passive"))
      (node (ref "IC2") (pin "6") (pinfunction "OSC_OUT/(PD1/CANTX)_6") (pintype "output"))
      (node (ref "Q2") (pin "2") (pinfunction "2_2") (pintype "passive"))
      (node (ref "R15") (pin "1") (pinfunction "1_1") (pintype "passive"))
    )
    (net (code "55") (name "PA0") (class "Default")
      (node (ref "C24") (pin "1") (pinfunction "1_1") (pintype "passive"))
      (node (ref "IC2") (pin "14") (pinfunction "PA0/WKUP/USART2_CTS/ADC12_IN0/TIM2_CH1_ETR_14") (pintype "bidirectional"))
      (node (ref "R12") (pin "2") (pinfunction "2_2") (pintype "passive"))
      (node (ref "R13") (pin "2") (pinfunction "2_2") (pintype "passive"))
      (node (ref "R14") (pin "2") (pinfunction "2_2") (pintype "passive"))
      (node (ref "R16") (pin "2") (pinfunction "2_2") (pintype "passive"))
      (node (ref "STMP1") (pin "39") (pinfunction "19_39") (pintype "passive"))
    )
    (net (code "56") (name "PA1") (class "Default")
      (node (ref "IC2") (pin "15") (pinfunction "PA1/USART2_RTS/ADC12_IN1/TIM2_CH2_15") (pintype "bidirectional"))
      (node (ref "R19") (pin "1") (pinfunction "1_1") (pintype "passive"))
      (node (ref "STMP1") (pin "38") (pinfunction "18_38") (pintype "passive"))
    )
    (net (code "57") (name "PA2") (class "Default")
      (node (ref "IC2") (pin "16") (pinfunction "PA2/USART2_TX/ADC12_IN2/TIM2_CH3_16") (pintype "bidirectional"))
      (node (ref "R17") (pin "1") (pinfunction "1_1") (pintype "passive"))
      (node (ref "STMP1") (pin "37") (pinfunction "17_37") (pintype "passive"))
    )
    (net (code "58") (name "PA3") (class "Default")
      (node (ref "IC2") (pin "17") (pinfunction "PA3/USART2_RX/ADC12_IN3/TIM2_CH4_17") (pintype "bidirectional"))
      (node (ref "STMP1") (pin "36") (pinfunction "16_36") (pintype "passive"))
    )
    (net (code "59") (name "PA4") (class "Default")
      (node (ref "IC2") (pin "20") (pinfunction "PA4/SPI1_NSS/ADC12_IN4/USART2_CK_20") (pintype "bidirectional"))
      (node (ref "R18") (pin "1") (pinfunction "1_1") (pintype "passive"))
      (node (ref "STMP1") (pin "35") (pinfunction "15_35") (pintype "passive"))
    )
    (net (code "60") (name "PA5") (class "Default")
      (node (ref "IC2") (pin "21") (pinfunction "PA5/SPI1_SCK/ADC12_IN5_21") (pintype "bidirectional"))
      (node (ref "STMP1") (pin "34") (pinfunction "14_34") (pintype "passive"))
    )
    (net (code "61") (name "PA6") (class "Default")
      (node (ref "IC2") (pin "22") (pinfunction "PA6/SPI1_MISO/ADC12_IN6/TIM3_CH1_22") (pintype "bidirectional"))
      (node (ref "STMP1") (pin "33") (pinfunction "13_33") (pintype "passive"))
    )
    (net (code "62") (name "PA7") (class "Default")
      (node (ref "IC2") (pin "23") (pinfunction "PA7SPI1_MOSI/ADC12_IN7/TIM3_CH2_23") (pintype "bidirectional"))
      (node (ref "STMP1") (pin "32") (pinfunction "12_32") (pintype "passive"))
    )
    (net (code "63") (name "PA8") (class "Default")
      (node (ref "IC2") (pin "41") (pinfunction "PA8/USART1_CK/MCO/TIM1_CH1_41") (pintype "bidirectional"))
      (node (ref "STMP1") (pin "25") (pinfunction "5_25") (pintype "passive"))
    )
    (net (code "64") (name "PA15") (class "Default")
      (node (ref "IC2") (pin "50") (pinfunction "JTDI/(TIM2_CH1_ETR/PA15/SPI1_NSS)_50") (pintype "bidirectional"))
      (node (ref "STMP1") (pin "24") (pinfunction "4_24") (pintype "passive"))
    )
    (net (code "65") (name "PB0") (class "Default")
      (node (ref "IC2") (pin "26") (pinfunction "PB0/ADC12_IN8/TIM3_CH3/(TIM1_CH2N)_26") (pintype "bidirectional"))
      (node (ref "R39") (pin "2") (pinfunction "2_2") (pintype "passive"))
    )
    (net (code "66") (name "PB1") (class "Default")
      (node (ref "IC2") (pin "27") (pinfunction "PB1/ADC12_IN9/TIM3_CH4/(TIM1_CH3N)_27") (pintype "bidirectional"))
      (node (ref "R40") (pin "2") (pinfunction "2_2") (pintype "passive"))
    )
    (net (code "67") (name "PB5") (class "Default")
      (node (ref "IC2") (pin "57") (pinfunction "PB5/I2C1_SMBA/(TIM3_CH2/SPI1_MOSI)_57") (pintype "bidirectional"))
      (node (ref "R7") (pin "1") (pinfunction "1_1") (pintype "passive"))
    )
    (net (code "68") (name "PC0") (class "Default")
      (node (ref "IC2") (pin "8") (pinfunction "PC0/ADC10_8") (pintype "bidirectional"))
      (node (ref "R33") (pin "2") (pinfunction "2_2") (pintype "passive"))
    )
    (net (code "69") (name "PC1") (class "Default")
      (node (ref "IC2") (pin "9") (pinfunction "PC1/ADC11_9") (pintype "bidirectional"))
      (node (ref "R34") (pin "2") (pinfunction "2_2") (pintype "passive"))
    )
    (net (code "70") (name "PC2") (class "Default")
      (node (ref "IC2") (pin "10") (pinfunction "PC2/ADC12_10") (pintype "bidirectional"))
      (node (ref "R35") (pin "2") (pinfunction "2_2") (pintype "passive"))
    )
    (net (code "71") (name "PC3") (class "Default")
      (node (ref "IC2") (pin "11") (pinfunction "PC3/ADC13_11") (pintype "bidirectional"))
      (node (ref "R36") (pin "2") (pinfunction "2_2") (pintype "passive"))
    )
    (net (code "72") (name "PC4") (class "Default")
      (node (ref "IC2") (pin "24") (pinfunction "PC4/ADC14_24") (pintype "bidirectional"))
      (node (ref "R37") (pin "2") (pinfunction "2_2") (pintype "passive"))
    )
    (net (code "73") (name "PC5") (class "Default")
      (node (ref "IC2") (pin "25") (pinfunction "PC5/ADC15_25") (pintype "bidirectional"))
      (node (ref "R38") (pin "2") (pinfunction "2_2") (pintype "passive"))
    )
    (net (code "74") (name "PC13") (class "Default")
      (node (ref "IC2") (pin "2") (pinfunction "PC13/TAMPER-RTC_2") (pintype "bidirectional"))
      (node (ref "STMP1") (pin "22") (pinfunction "2_22") (pintype "passive"))
    )
    (net (code "75") (name "PD2") (class "Default")
      (node (ref "IC2") (pin "54") (pinfunction "PD2/TIM3_ETR_54") (pintype "bidirectional"))
      (node (ref "R22") (pin "2") (pinfunction "2_2") (pintype "passive"))
      (node (ref "STMP1") (pin "23") (pinfunction "3_23") (pintype "passive"))
    )
    (net (code "76") (name "RS485_A") (class "Default")
      (node (ref "F2") (pin "P$2") (pinfunction "2_P$2") (pintype "passive"))
      (node (ref "R48") (pin "1") (pinfunction "1_1") (pintype "passive"))
      (node (ref "X1") (pin "2") (pinfunction "SK_2") (pintype "passive"))
    )
    (net (code "77") (name "RS485_B") (class "Default")
      (node (ref "F1") (pin "P$2") (pinfunction "2_P$2") (pintype "passive"))
      (node (ref "S1") (pin "7") (pinfunction "7_7") (pintype "passive"))
      (node (ref "X1") (pin "1") (pinfunction "SK_1") (pintype "passive"))
    )
    (net (code "78") (name "RXD1") (class "Default")
      (node (ref "IC2") (pin "43") (pinfunction "PA10/USART1_RX/TIM1_CH3_43") (pintype "bidirectional"))
      (node (ref "JP1") (pin "3") (pinfunction "3_3") (pintype "passive"))
      (node (ref "R23") (pin "1") (pinfunction "1_1") (pintype "passive"))
    )
    (net (code "79") (name "RXD3") (class "Default")
      (node (ref "IC2") (pin "52") (pinfunction "PC11/(USART3_RX)_52") (pintype "bidirectional"))
      (node (ref "IC4") (pin "1") (pinfunction "RO_1") (pintype "output"))
    )
    (net (code "80") (name "SCL2") (class "Default")
      (node (ref "IC1") (pin "6") (pinfunction "SCL_6") (pintype "bidirectional"))
      (node (ref "IC2") (pin "29") (pinfunction "PB10/I2C2_SCL/USART3_TX/(TIM2_CH3)_29") (pintype "bidirectional"))
      (node (ref "R3") (pin "1") (pinfunction "1_1") (pintype "passive"))
      (node (ref "STMP1") (pin "31") (pinfunction "11_31") (pintype "passive"))
    )
    (net (code "81") (name "SDA2") (class "Default")
      (node (ref "IC1") (pin "5") (pinfunction "SDA_5") (pintype "bidirectional"))
      (node (ref "IC2") (pin "30") (pinfunction "PB11/I2C2_SDA/USART3_RX/(TIM2_CH4)_30") (pintype "bidirectional"))
      (node (ref "R4") (pin "1") (pinfunction "1_1") (pintype "passive"))
      (node (ref "STMP1") (pin "30") (pinfunction "10_30") (pintype "passive"))
    )
    (net (code "82") (name "SPI2_MISO") (class "Default")
      (node (ref "IC2") (pin "35") (pinfunction "PB14/SPI2_MISO/TIM1_CH2N/USART3_RTS_35") (pintype "bidirectional"))
      (node (ref "STMP1") (pin "27") (pinfunction "7_27") (pintype "passive"))
    )
    (net (code "83") (name "SPI2_MOSI") (class "Default")
      (node (ref "IC2") (pin "36") (pinfunction "PB15/SPI2_MOSI/TIM1_CH3N_36") (pintype "bidirectional"))
      (node (ref "STMP1") (pin "26") (pinfunction "6_26") (pintype "passive"))
    )
    (net (code "84") (name "SPI2_NSS") (class "Default")
      (node (ref "IC2") (pin "33") (pinfunction "PB12/SPI2_NSS/I2C2_SMBAI/TIM1_BKIN/USART3_CK_33") (pintype "bidirectional"))
      (node (ref "STMP1") (pin "29") (pinfunction "9_29") (pintype "passive"))
    )
    (net (code "85") (name "SPI2_SCLK") (class "Default")
      (node (ref "IC2") (pin "34") (pinfunction "PB13/SPI2_SCK/TIM1_CH1N/USART3_CTS_34") (pintype "bidirectional"))
      (node (ref "STMP1") (pin "28") (pinfunction "8_28") (pintype "passive"))
    )
    (net (code "86") (name "SW3") (class "Default")
      (node (ref "IC2") (pin "55") (pinfunction "JTDO/(TIM2_CH2/PB3/TRACESWO/SPI1_SCK)_55") (pintype "bidirectional"))
      (node (ref "R50") (pin "2") (pinfunction "2_2") (pintype "passive"))
    )
    (net (code "87") (name "SW4") (class "Default")
      (node (ref "IC2") (pin "56") (pinfunction "JTNRST/(PB4/TIM3_CH1/SPI1_MISO)_56") (pintype "bidirectional"))
      (node (ref "R51") (pin "2") (pinfunction "2_2") (pintype "passive"))
    )
    (net (code "88") (name "SWCLK") (class "Default")
      (node (ref "IC2") (pin "49") (pinfunction "JTCK-SWCLK/(PA14)_49") (pintype "bidirectional"))
      (node (ref "R1") (pin "1") (pinfunction "1_1") (pintype "passive"))
      (node (ref "SWD1") (pin "2") (pinfunction "2_2") (pintype "passive"))
    )
    (net (code "89") (name "SWDIO") (class "Default")
      (node (ref "IC2") (pin "46") (pinfunction "JTMS-SWDIO/(PA13)_46") (pintype "bidirectional"))
      (node (ref "R2") (pin "1") (pinfunction "1_1") (pintype "passive"))
      (node (ref "SWD1") (pin "4") (pinfunction "4_4") (pintype "passive"))
    )
    (net (code "90") (name "TIM3_CH1") (class "Default")
      (node (ref "IC2") (pin "37") (pinfunction "PC6/(TIM3_CH1)_37") (pintype "bidirectional"))
      (node (ref "R25") (pin "2") (pinfunction "2_2") (pintype "passive"))
    )
    (net (code "91") (name "TIM3_CH2") (class "Default")
      (node (ref "IC2") (pin "38") (pinfunction "PC7/(TIM3_CH2)_38") (pintype "bidirectional"))
      (node (ref "R26") (pin "2") (pinfunction "2_2") (pintype "passive"))
    )
    (net (code "92") (name "TIM3_CH3") (class "Default")
      (node (ref "IC2") (pin "39") (pinfunction "PC8/(TIM3_CH3)_39") (pintype "bidirectional"))
      (node (ref "R27") (pin "2") (pinfunction "2_2") (pintype "passive"))
    )
    (net (code "93") (name "TIM3_CH4") (class "Default")
      (node (ref "IC2") (pin "40") (pinfunction "PC9/(TIM3_CH4)_40") (pintype "bidirectional"))
      (node (ref "R28") (pin "2") (pinfunction "2_2") (pintype "passive"))
    )
    (net (code "94") (name "TIM4_CH1") (class "Default")
      (node (ref "IC2") (pin "58") (pinfunction "PB6/I2C1_SCL/TIM4_CH1/(USART1_TX)_58") (pintype "bidirectional"))
      (node (ref "R29") (pin "2") (pinfunction "2_2") (pintype "passive"))
    )
    (net (code "95") (name "TIM4_CH2") (class "Default")
      (node (ref "IC2") (pin "59") (pinfunction "PB7/I2C1_SDA/TIM4_CH2/(USART1_RX)_59") (pintype "bidirectional"))
      (node (ref "R30") (pin "2") (pinfunction "2_2") (pintype "passive"))
    )
    (net (code "96") (name "TIM4_CH3") (class "Default")
      (node (ref "IC2") (pin "61") (pinfunction "PB8/TIM4_CH3/(I2C1_SCL/CANRX)_61") (pintype "bidirectional"))
      (node (ref "R31") (pin "2") (pinfunction "2_2") (pintype "passive"))
    )
    (net (code "97") (name "TIM4_CH4") (class "Default")
      (node (ref "IC2") (pin "62") (pinfunction "PB9/TIM4_CH4/(I2C1_SDA/CANTX)_62") (pintype "bidirectional"))
      (node (ref "R32") (pin "2") (pinfunction "2_2") (pintype "passive"))
    )
    (net (code "98") (name "TXD1") (class "Default")
      (node (ref "IC2") (pin "42") (pinfunction "PA9/USART1_TX/TIM1_CH2_42") (pintype "bidirectional"))
      (node (ref "JP1") (pin "2") (pinfunction "2_2") (pintype "passive"))
    )
    (net (code "99") (name "TXD3") (class "Default")
      (node (ref "IC2") (pin "51") (pinfunction "PC10/(USART3_TX)_51") (pintype "bidirectional"))
      (node (ref "IC4") (pin "2") (pinfunction "RE/_2") (pintype "input"))
      (node (ref "IC4") (pin "3") (pinfunction "DE_3") (pintype "input"))
      (node (ref "R41") (pin "2") (pinfunction "2_2") (pintype "passive"))
    )
    (net (code "100") (name "VBAT") (class "Default")
      (node (ref "G1") (pin "+") (pinfunction "+_+") (pintype "passive"))
      (node (ref "IC2") (pin "1") (pinfunction "VBAT_1") (pintype "power_in"))
    )
    (net (code "101") (name "VDDA") (class "Default")
      (node (ref "C11") (pin "1") (pinfunction "1_1") (pintype "passive"))
      (node (ref "IC2") (pin "13") (pinfunction "VDDA_13") (pintype "power_in"))
      (node (ref "L1") (pin "2") (pinfunction "2_2") (pintype "passive"))
      (node (ref "SW3") (pin "1") (pinfunction "P_1") (pintype "passive"))
      (node (ref "SW4") (pin "1") (pinfunction "P_1") (pintype "passive"))
      (node (ref "SW5") (pin "1") (pinfunction "P_1") (pintype "passive"))
    )
    (net (code "102") (name "unconnected-(SWD1-Pad6)") (class "Default")
      (node (ref "SWD1") (pin "6") (pinfunction "6_6") (pintype "passive"))
    )
    (net (code "103") (name "unconnected-(U1-MASS-Pad4)") (class "Default")
      (node (ref "U1") (pin "4") (pinfunction "MASS_4") (pintype "passive"))
    )
    (net (code "104") (name "~{LCD_CS}") (class "Default")
      (node (ref "LCD1") (pin "2") (pinfunction "~{CS}_2") (pintype "input"))
      (node (ref "R19") (pin "2") (pinfunction "2_2") (pintype "passive"))
      (node (ref "R20") (pin "1") (pinfunction "1_1") (pintype "passive"))
    )
    (net (code "105") (name "~{RESET}") (class "Default")
      (node (ref "C3") (pin "1") (pinfunction "1_1") (pintype "passive"))
      (node (ref "IC2") (pin "7") (pinfunction "~{RESET}_7") (pintype "input"))
      (node (ref "LCD1") (pin "1") (pinfunction "~{RST}_1") (pintype "input"))
      (node (ref "R11") (pin "1") (pinfunction "1_1") (pintype "passive"))
      (node (ref "SW1") (pin "2") (pinfunction "S_2") (pintype "passive"))
      (node (ref "SWD1") (pin "5") (pinfunction "5_5") (pintype "passive"))
    )
  )
)
